# ou6_cs-ctrl_V1_0.net
KiCad netlist of a schematic drawn in EAGLE
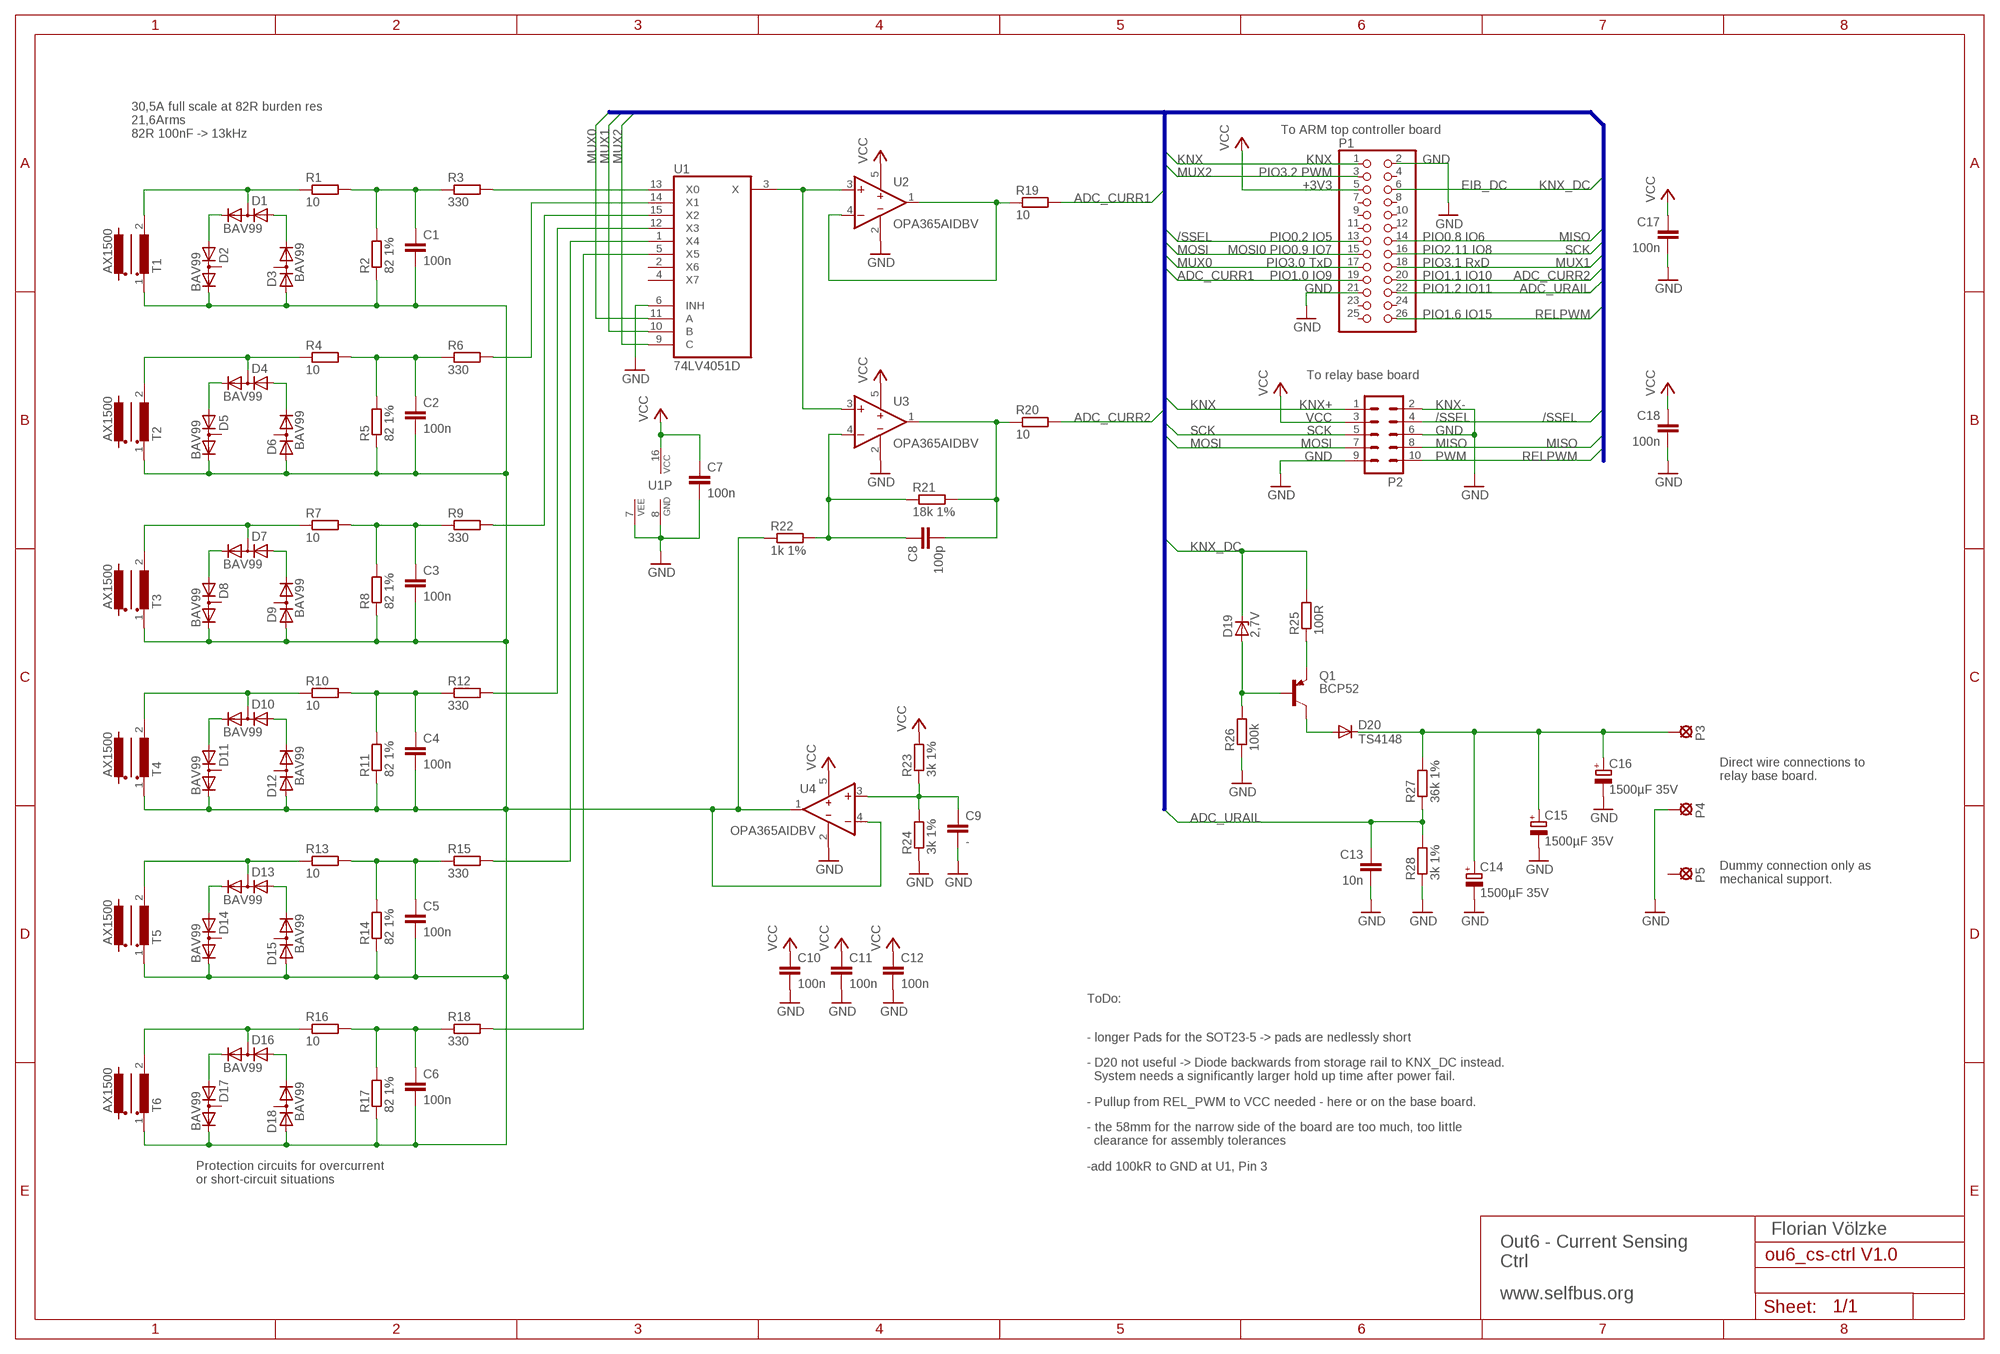
[diagram p0: schematic, sheet 1]

(export (version "E")
  (design (tool "Eeschema 10.0.6"))
  (components
    (comp (ref "C1")
      (value "100n")
      (footprint "eagle-import:R0805M")
      (libsource (lib "eagle-import") (part "C-EUC0805M"))
    )
    (comp (ref "C2")
      (value "100n")
      (footprint "eagle-import:R0805M")
      (libsource (lib "eagle-import") (part "C-EUC0805M"))
    )
    (comp (ref "C3")
      (value "100n")
      (footprint "eagle-import:R0805M")
      (libsource (lib "eagle-import") (part "C-EUC0805M"))
    )
    (comp (ref "C4")
      (value "100n")
      (footprint "eagle-import:R0805M")
      (libsource (lib "eagle-import") (part "C-EUC0805M"))
    )
    (comp (ref "C5")
      (value "100n")
      (footprint "eagle-import:R0805M")
      (libsource (lib "eagle-import") (part "C-EUC0805M"))
    )
    (comp (ref "C6")
      (value "100n")
      (footprint "eagle-import:R0805M")
      (libsource (lib "eagle-import") (part "C-EUC0805M"))
    )
    (comp (ref "C7")
      (value "100n")
      (footprint "eagle-import:R0805M")
      (libsource (lib "eagle-import") (part "C-EUC0805M"))
    )
    (comp (ref "C8")
      (value "100p")
      (footprint "eagle-import:R0805M")
      (libsource (lib "eagle-import") (part "C-EUC0805M"))
    )
    (comp (ref "C9")
      (value "-")
      (footprint "eagle-import:R0805M")
      (libsource (lib "eagle-import") (part "C-EUC0805M"))
    )
    (comp (ref "C10")
      (value "100n")
      (footprint "eagle-import:R0805M")
      (libsource (lib "eagle-import") (part "C-EUC0805M"))
    )
    (comp (ref "C11")
      (value "100n")
      (footprint "eagle-import:R0805M")
      (libsource (lib "eagle-import") (part "C-EUC0805M"))
    )
    (comp (ref "C12")
      (value "100n")
      (footprint "eagle-import:R0805M")
      (libsource (lib "eagle-import") (part "C-EUC0805M"))
    )
    (comp (ref "C13")
      (value "10n")
      (footprint "eagle-import:R0805M")
      (libsource (lib "eagle-import") (part "C-EUC0805M"))
    )
    (comp (ref "C14")
      (value "1500µF 35V")
      (footprint "eagle-import:E5-13-30")
      (libsource (lib "eagle-import") (part "CPOL-EUE5-13-30"))
    )
    (comp (ref "C15")
      (value "1500µF 35V")
      (footprint "eagle-import:E5-13-30")
      (libsource (lib "eagle-import") (part "CPOL-EUE5-13-30"))
    )
    (comp (ref "C16")
      (value "1500µF 35V")
      (footprint "eagle-import:E5-13-30")
      (libsource (lib "eagle-import") (part "CPOL-EUE5-13-30"))
    )
    (comp (ref "C17")
      (value "100n")
      (footprint "eagle-import:R0805M")
      (libsource (lib "eagle-import") (part "C-EUC0805M"))
    )
    (comp (ref "C18")
      (value "100n")
      (footprint "eagle-import:R0805M")
      (libsource (lib "eagle-import") (part "C-EUC0805M"))
    )
    (comp (ref "D1")
      (value "BAV99")
      (footprint "eagle-import:SOT23")
      (libsource (lib "eagle-import") (part "DIODE_2CACA-SOT23"))
    )
    (comp (ref "D2")
      (value "BAV99")
      (footprint "eagle-import:SOT23")
      (libsource (lib "eagle-import") (part "DIODE_2CACA-SOT23"))
    )
    (comp (ref "D3")
      (value "BAV99")
      (footprint "eagle-import:SOT23")
      (libsource (lib "eagle-import") (part "DIODE_2CACA-SOT23"))
    )
    (comp (ref "D4")
      (value "BAV99")
      (footprint "eagle-import:SOT23")
      (libsource (lib "eagle-import") (part "DIODE_2CACA-SOT23"))
    )
    (comp (ref "D5")
      (value "BAV99")
      (footprint "eagle-import:SOT23")
      (libsource (lib "eagle-import") (part "DIODE_2CACA-SOT23"))
    )
    (comp (ref "D6")
      (value "BAV99")
      (footprint "eagle-import:SOT23")
      (libsource (lib "eagle-import") (part "DIODE_2CACA-SOT23"))
    )
    (comp (ref "D7")
      (value "BAV99")
      (footprint "eagle-import:SOT23")
      (libsource (lib "eagle-import") (part "DIODE_2CACA-SOT23"))
    )
    (comp (ref "D8")
      (value "BAV99")
      (footprint "eagle-import:SOT23")
      (libsource (lib "eagle-import") (part "DIODE_2CACA-SOT23"))
    )
    (comp (ref "D9")
      (value "BAV99")
      (footprint "eagle-import:SOT23")
      (libsource (lib "eagle-import") (part "DIODE_2CACA-SOT23"))
    )
    (comp (ref "D10")
      (value "BAV99")
      (footprint "eagle-import:SOT23")
      (libsource (lib "eagle-import") (part "DIODE_2CACA-SOT23"))
    )
    (comp (ref "D11")
      (value "BAV99")
      (footprint "eagle-import:SOT23")
      (libsource (lib "eagle-import") (part "DIODE_2CACA-SOT23"))
    )
    (comp (ref "D12")
      (value "BAV99")
      (footprint "eagle-import:SOT23")
      (libsource (lib "eagle-import") (part "DIODE_2CACA-SOT23"))
    )
    (comp (ref "D13")
      (value "BAV99")
      (footprint "eagle-import:SOT23")
      (libsource (lib "eagle-import") (part "DIODE_2CACA-SOT23"))
    )
    (comp (ref "D14")
      (value "BAV99")
      (footprint "eagle-import:SOT23")
      (libsource (lib "eagle-import") (part "DIODE_2CACA-SOT23"))
    )
    (comp (ref "D15")
      (value "BAV99")
      (footprint "eagle-import:SOT23")
      (libsource (lib "eagle-import") (part "DIODE_2CACA-SOT23"))
    )
    (comp (ref "D16")
      (value "BAV99")
      (footprint "eagle-import:SOT23")
      (libsource (lib "eagle-import") (part "DIODE_2CACA-SOT23"))
    )
    (comp (ref "D17")
      (value "BAV99")
      (footprint "eagle-import:SOT23")
      (libsource (lib "eagle-import") (part "DIODE_2CACA-SOT23"))
    )
    (comp (ref "D18")
      (value "BAV99")
      (footprint "eagle-import:SOT23")
      (libsource (lib "eagle-import") (part "DIODE_2CACA-SOT23"))
    )
    (comp (ref "D19")
      (value "2,7V")
      (footprint "eagle-import:SOT23")
      (libsource (lib "eagle-import") (part "ZENER-DIODESOT23"))
    )
    (comp (ref "D20")
      (value "TS4148")
      (footprint "eagle-import:MINIMELF")
      (libsource (lib "eagle-import") (part "DIODE-MINIMELF"))
    )
    (comp (ref "P1")
      (value "PINHD-2X13SMD")
      (footprint "eagle-import:2X13SMD")
      (libsource (lib "eagle-import") (part "PINHD-2X13SMD"))
    )
    (comp (ref "P2")
      (value "ML10")
      (footprint "eagle-import:ML10")
      (libsource (lib "eagle-import") (part "ML10"))
    )
    (comp (ref "P3")
      (value "SE1.5")
      (footprint "eagle-import:SE15")
      (libsource (lib "eagle-import") (part "SE1.5"))
    )
    (comp (ref "P4")
      (value "SE1.5")
      (footprint "eagle-import:SE15")
      (libsource (lib "eagle-import") (part "SE1.5"))
    )
    (comp (ref "P5")
      (value "SE1.5")
      (footprint "eagle-import:SE15")
      (libsource (lib "eagle-import") (part "SE1.5"))
    )
    (comp (ref "Q1")
      (value "BCP52")
      (footprint "eagle-import:SOT223")
      (libsource (lib "eagle-import") (part "FZT753SMD"))
    )
    (comp (ref "R1")
      (value "10")
      (footprint "eagle-import:R0805M")
      (libsource (lib "eagle-import") (part "R-EU_R0805M"))
    )
    (comp (ref "R2")
      (value "82 1%")
      (footprint "eagle-import:R0805M")
      (libsource (lib "eagle-import") (part "R-EU_R0805M"))
    )
    (comp (ref "R3")
      (value "330")
      (footprint "eagle-import:R0805M")
      (libsource (lib "eagle-import") (part "R-EU_R0805M"))
    )
    (comp (ref "R4")
      (value "10")
      (footprint "eagle-import:R0805M")
      (libsource (lib "eagle-import") (part "R-EU_R0805M"))
    )
    (comp (ref "R5")
      (value "82 1%")
      (footprint "eagle-import:R0805M")
      (libsource (lib "eagle-import") (part "R-EU_R0805M"))
    )
    (comp (ref "R6")
      (value "330")
      (footprint "eagle-import:R0805M")
      (libsource (lib "eagle-import") (part "R-EU_R0805M"))
    )
    (comp (ref "R7")
      (value "10")
      (footprint "eagle-import:R0805M")
      (libsource (lib "eagle-import") (part "R-EU_R0805M"))
    )
    (comp (ref "R8")
      (value "82 1%")
      (footprint "eagle-import:R0805M")
      (libsource (lib "eagle-import") (part "R-EU_R0805M"))
    )
    (comp (ref "R9")
      (value "330")
      (footprint "eagle-import:R0805M")
      (libsource (lib "eagle-import") (part "R-EU_R0805M"))
    )
    (comp (ref "R10")
      (value "10")
      (footprint "eagle-import:R0805M")
      (libsource (lib "eagle-import") (part "R-EU_R0805M"))
    )
    (comp (ref "R11")
      (value "82 1%")
      (footprint "eagle-import:R0805M")
      (libsource (lib "eagle-import") (part "R-EU_R0805M"))
    )
    (comp (ref "R12")
      (value "330")
      (footprint "eagle-import:R0805M")
      (libsource (lib "eagle-import") (part "R-EU_R0805M"))
    )
    (comp (ref "R13")
      (value "10")
      (footprint "eagle-import:R0805M")
      (libsource (lib "eagle-import") (part "R-EU_R0805M"))
    )
    (comp (ref "R14")
      (value "82 1%")
      (footprint "eagle-import:R0805M")
      (libsource (lib "eagle-import") (part "R-EU_R0805M"))
    )
    (comp (ref "R15")
      (value "330")
      (footprint "eagle-import:R0805M")
      (libsource (lib "eagle-import") (part "R-EU_R0805M"))
    )
    (comp (ref "R16")
      (value "10")
      (footprint "eagle-import:R0805M")
      (libsource (lib "eagle-import") (part "R-EU_R0805M"))
    )
    (comp (ref "R17")
      (value "82 1%")
      (footprint "eagle-import:R0805M")
      (libsource (lib "eagle-import") (part "R-EU_R0805M"))
    )
    (comp (ref "R18")
      (value "330")
      (footprint "eagle-import:R0805M")
      (libsource (lib "eagle-import") (part "R-EU_R0805M"))
    )
    (comp (ref "R19")
      (value "10")
      (footprint "eagle-import:R0805M")
      (libsource (lib "eagle-import") (part "R-EU_R0805M"))
    )
    (comp (ref "R20")
      (value "10")
      (footprint "eagle-import:R0805M")
      (libsource (lib "eagle-import") (part "R-EU_R0805M"))
    )
    (comp (ref "R21")
      (value "18k 1%")
      (footprint "eagle-import:R0805M")
      (libsource (lib "eagle-import") (part "R-EU_R0805M"))
    )
    (comp (ref "R22")
      (value "1k 1%")
      (footprint "eagle-import:R0805M")
      (libsource (lib "eagle-import") (part "R-EU_R0805M"))
    )
    (comp (ref "R23")
      (value "3k 1%")
      (footprint "eagle-import:R0805M")
      (libsource (lib "eagle-import") (part "R-EU_R0805M"))
    )
    (comp (ref "R24")
      (value "3k 1%")
      (footprint "eagle-import:R0805M")
      (libsource (lib "eagle-import") (part "R-EU_R0805M"))
    )
    (comp (ref "R25")
      (value "100R")
      (footprint "eagle-import:R0805M")
      (libsource (lib "eagle-import") (part "R-EU_R0805M"))
    )
    (comp (ref "R26")
      (value "100k")
      (footprint "eagle-import:R0805M")
      (libsource (lib "eagle-import") (part "R-EU_R0805M"))
    )
    (comp (ref "R27")
      (value "36k 1%")
      (footprint "eagle-import:R0805M")
      (libsource (lib "eagle-import") (part "R-EU_R0805M"))
    )
    (comp (ref "R28")
      (value "3k 1%")
      (footprint "eagle-import:R0805M")
      (libsource (lib "eagle-import") (part "R-EU_R0805M"))
    )
    (comp (ref "T1")
      (value "AX1500")
      (footprint "eagle-import:SMALLXFORMER")
      (libsource (lib "eagle-import") (part "STROMWANDLERTALEMA_AX1500"))
    )
    (comp (ref "T2")
      (value "AX1500")
      (footprint "eagle-import:SMALLXFORMER")
      (libsource (lib "eagle-import") (part "STROMWANDLERTALEMA_AX1500"))
    )
    (comp (ref "T3")
      (value "AX1500")
      (footprint "eagle-import:SMALLXFORMER")
      (libsource (lib "eagle-import") (part "STROMWANDLERTALEMA_AX1500"))
    )
    (comp (ref "T4")
      (value "AX1500")
      (footprint "eagle-import:SMALLXFORMER")
      (libsource (lib "eagle-import") (part "STROMWANDLERTALEMA_AX1500"))
    )
    (comp (ref "T5")
      (value "AX1500")
      (footprint "eagle-import:SMALLXFORMER")
      (libsource (lib "eagle-import") (part "STROMWANDLERTALEMA_AX1500"))
    )
    (comp (ref "T6")
      (value "AX1500")
      (footprint "eagle-import:SMALLXFORMER")
      (libsource (lib "eagle-import") (part "STROMWANDLERTALEMA_AX1500"))
    )
    (comp (ref "U1")
      (value "74LV4051D")
      (footprint "eagle-import:SO16")
      (libsource (lib "eagle-import") (part "4051D"))
    )
    (comp (ref "U2")
      (value "OPA365AIDBV")
      (footprint "eagle-import:SOT23-5")
      (libsource (lib "eagle-import") (part "LTC2050CS5"))
    )
    (comp (ref "U3")
      (value "OPA365AIDBV")
      (footprint "eagle-import:SOT23-5")
      (libsource (lib "eagle-import") (part "LTC2050CS5"))
    )
    (comp (ref "U4")
      (value "OPA365AIDBV")
      (footprint "eagle-import:SOT23-5")
      (libsource (lib "eagle-import") (part "LTC2050CS5"))
    )
  )
  (nets
    (net (code "1") (name "/ADC_CURR1") (class "Default")
      (node (ref "P1") (pin "19") (pinfunction "19_19") (pintype "passive"))
      (node (ref "R19") (pin "2") (pinfunction "2_2") (pintype "passive"))
    )
    (net (code "2") (name "/ADC_CURR2") (class "Default")
      (node (ref "P1") (pin "20") (pinfunction "20_20") (pintype "passive"))
      (node (ref "R20") (pin "2") (pinfunction "2_2") (pintype "passive"))
    )
    (net (code "3") (name "/ADC_URAIL") (class "Default")
      (node (ref "C13") (pin "1") (pinfunction "1_1") (pintype "passive"))
      (node (ref "P1") (pin "22") (pinfunction "22_22") (pintype "passive"))
      (node (ref "R27") (pin "1") (pinfunction "1_1") (pintype "passive"))
      (node (ref "R28") (pin "2") (pinfunction "2_2") (pintype "passive"))
    )
    (net (code "4") (name "/KNX") (class "Default")
      (node (ref "P1") (pin "1") (pinfunction "1_1") (pintype "passive"))
      (node (ref "P2") (pin "1") (pinfunction "1_1") (pintype "passive"))
    )
    (net (code "5") (name "/KNX_DC") (class "Default")
      (node (ref "D19") (pin "3") (pinfunction "C_3") (pintype "passive"))
      (node (ref "P1") (pin "6") (pinfunction "6_6") (pintype "passive"))
      (node (ref "R25") (pin "2") (pinfunction "2_2") (pintype "passive"))
    )
    (net (code "6") (name "/MISO") (class "Default")
      (node (ref "P1") (pin "14") (pinfunction "14_14") (pintype "passive"))
      (node (ref "P2") (pin "8") (pinfunction "8_8") (pintype "passive"))
    )
    (net (code "7") (name "/MOSI") (class "Default")
      (node (ref "P1") (pin "15") (pinfunction "15_15") (pintype "passive"))
      (node (ref "P2") (pin "7") (pinfunction "7_7") (pintype "passive"))
    )
    (net (code "8") (name "/MUX0") (class "Default")
      (node (ref "P1") (pin "17") (pinfunction "17_17") (pintype "passive"))
      (node (ref "U1") (pin "11") (pinfunction "A_11") (pintype "input"))
    )
    (net (code "9") (name "/MUX1") (class "Default")
      (node (ref "P1") (pin "18") (pinfunction "18_18") (pintype "passive"))
      (node (ref "U1") (pin "10") (pinfunction "B_10") (pintype "input"))
    )
    (net (code "10") (name "/MUX2") (class "Default")
      (node (ref "P1") (pin "3") (pinfunction "3_3") (pintype "passive"))
      (node (ref "U1") (pin "9") (pinfunction "C_9") (pintype "input"))
    )
    (net (code "11") (name "/RELPWM") (class "Default")
      (node (ref "P1") (pin "26") (pinfunction "26_26") (pintype "passive"))
      (node (ref "P2") (pin "10") (pinfunction "10_10") (pintype "passive"))
    )
    (net (code "12") (name "/SCK") (class "Default")
      (node (ref "P1") (pin "16") (pinfunction "16_16") (pintype "passive"))
      (node (ref "P2") (pin "5") (pinfunction "5_5") (pintype "passive"))
    )
    (net (code "13") (name "/{slash}SSEL") (class "Default")
      (node (ref "P1") (pin "13") (pinfunction "13_13") (pintype "passive"))
      (node (ref "P2") (pin "4") (pinfunction "4_4") (pintype "passive"))
    )
    (net (code "14") (name "GND") (class "Default")
      (node (ref "C10") (pin "2") (pinfunction "2_2") (pintype "passive"))
      (node (ref "C11") (pin "2") (pinfunction "2_2") (pintype "passive"))
      (node (ref "C12") (pin "2") (pinfunction "2_2") (pintype "passive"))
      (node (ref "C13") (pin "2") (pinfunction "2_2") (pintype "passive"))
      (node (ref "C14") (pin "-") (pinfunction "-_-") (pintype "passive"))
      (node (ref "C15") (pin "-") (pinfunction "-_-") (pintype "passive"))
      (node (ref "C16") (pin "-") (pinfunction "-_-") (pintype "passive"))
      (node (ref "C17") (pin "2") (pinfunction "2_2") (pintype "passive"))
      (node (ref "C18") (pin "2") (pinfunction "2_2") (pintype "passive"))
      (node (ref "C7") (pin "2") (pinfunction "2_2") (pintype "passive"))
      (node (ref "C9") (pin "2") (pinfunction "2_2") (pintype "passive"))
      (node (ref "P1") (pin "2") (pinfunction "2_2") (pintype "passive"))
      (node (ref "P1") (pin "21") (pinfunction "21_21") (pintype "passive"))
      (node (ref "P2") (pin "2") (pinfunction "2_2") (pintype "passive"))
      (node (ref "P2") (pin "6") (pinfunction "6_6") (pintype "passive"))
      (node (ref "P2") (pin "9") (pinfunction "9_9") (pintype "passive"))
      (node (ref "P4") (pin "MP") (pinfunction "MP_MP") (pintype "passive"))
      (node (ref "R24") (pin "1") (pinfunction "1_1") (pintype "passive"))
      (node (ref "R26") (pin "1") (pinfunction "1_1") (pintype "passive"))
      (node (ref "R28") (pin "1") (pinfunction "1_1") (pintype "passive"))
      (node (ref "U1") (pin "6") (pinfunction "INH_6") (pintype "input"))
      (node (ref "U1") (pin "7") (pinfunction "VEE_7") (pintype "power_in"))
      (node (ref "U1") (pin "8") (pinfunction "GND_8") (pintype "power_in"))
      (node (ref "U2") (pin "2") (pinfunction "V-_2") (pintype "power_in"))
      (node (ref "U3") (pin "2") (pinfunction "V-_2") (pintype "power_in"))
      (node (ref "U4") (pin "2") (pinfunction "V-_2") (pintype "power_in"))
    )
    (net (code "15") (name "Net-(C1-Pad1)") (class "Default")
      (node (ref "C1") (pin "1") (pinfunction "1_1") (pintype "passive"))
      (node (ref "R1") (pin "2") (pinfunction "2_2") (pintype "passive"))
      (node (ref "R2") (pin "2") (pinfunction "2_2") (pintype "passive"))
      (node (ref "R3") (pin "1") (pinfunction "1_1") (pintype "passive"))
    )
    (net (code "16") (name "Net-(C2-Pad1)") (class "Default")
      (node (ref "C2") (pin "1") (pinfunction "1_1") (pintype "passive"))
      (node (ref "R4") (pin "2") (pinfunction "2_2") (pintype "passive"))
      (node (ref "R5") (pin "2") (pinfunction "2_2") (pintype "passive"))
      (node (ref "R6") (pin "1") (pinfunction "1_1") (pintype "passive"))
    )
    (net (code "17") (name "Net-(C3-Pad1)") (class "Default")
      (node (ref "C3") (pin "1") (pinfunction "1_1") (pintype "passive"))
      (node (ref "R7") (pin "2") (pinfunction "2_2") (pintype "passive"))
      (node (ref "R8") (pin "2") (pinfunction "2_2") (pintype "passive"))
      (node (ref "R9") (pin "1") (pinfunction "1_1") (pintype "passive"))
    )
    (net (code "18") (name "Net-(C4-Pad1)") (class "Default")
      (node (ref "C4") (pin "1") (pinfunction "1_1") (pintype "passive"))
      (node (ref "R10") (pin "2") (pinfunction "2_2") (pintype "passive"))
      (node (ref "R11") (pin "2") (pinfunction "2_2") (pintype "passive"))
      (node (ref "R12") (pin "1") (pinfunction "1_1") (pintype "passive"))
    )
    (net (code "19") (name "Net-(C5-Pad1)") (class "Default")
      (node (ref "C5") (pin "1") (pinfunction "1_1") (pintype "passive"))
      (node (ref "R13") (pin "2") (pinfunction "2_2") (pintype "passive"))
      (node (ref "R14") (pin "2") (pinfunction "2_2") (pintype "passive"))
      (node (ref "R15") (pin "1") (pinfunction "1_1") (pintype "passive"))
    )
    (net (code "20") (name "Net-(C6-Pad1)") (class "Default")
      (node (ref "C6") (pin "1") (pinfunction "1_1") (pintype "passive"))
      (node (ref "R16") (pin "2") (pinfunction "2_2") (pintype "passive"))
      (node (ref "R17") (pin "2") (pinfunction "2_2") (pintype "passive"))
      (node (ref "R18") (pin "1") (pinfunction "1_1") (pintype "passive"))
    )
    (net (code "21") (name "Net-(C14-Pad+)") (class "Default")
      (node (ref "C14") (pin "+") (pinfunction "+_+") (pintype "passive"))
      (node (ref "C15") (pin "+") (pinfunction "+_+") (pintype "passive"))
      (node (ref "C16") (pin "+") (pinfunction "+_+") (pintype "passive"))
      (node (ref "D20") (pin "C") (pinfunction "C_C") (pintype "passive"))
      (node (ref "P3") (pin "MP") (pinfunction "MP_MP") (pintype "passive"))
      (node (ref "R27") (pin "2") (pinfunction "2_2") (pintype "passive"))
    )
    (net (code "22") (name "Net-(D1-A)") (class "Default")
      (node (ref "D1") (pin "1") (pinfunction "A_1") (pintype "passive"))
      (node (ref "D3") (pin "2") (pinfunction "C_2") (pintype "passive"))
    )
    (net (code "23") (name "Net-(D1-AC)") (class "Default")
      (node (ref "D1") (pin "3") (pinfunction "AC_3") (pintype "passive"))
      (node (ref "R1") (pin "1") (pinfunction "1_1") (pintype "passive"))
      (node (ref "T1") (pin "2") (pinfunction "W1E_2") (pintype "passive"))
    )
    (net (code "24") (name "Net-(D1-C)") (class "Default")
      (node (ref "D1") (pin "2") (pinfunction "C_2") (pintype "passive"))
      (node (ref "D2") (pin "1") (pinfunction "A_1") (pintype "passive"))
    )
    (net (code "25") (name "Net-(D4-A)") (class "Default")
      (node (ref "D4") (pin "1") (pinfunction "A_1") (pintype "passive"))
      (node (ref "D6") (pin "2") (pinfunction "C_2") (pintype "passive"))
    )
    (net (code "26") (name "Net-(D4-AC)") (class "Default")
      (node (ref "D4") (pin "3") (pinfunction "AC_3") (pintype "passive"))
      (node (ref "R4") (pin "1") (pinfunction "1_1") (pintype "passive"))
      (node (ref "T2") (pin "2") (pinfunction "W1E_2") (pintype "passive"))
    )
    (net (code "27") (name "Net-(D4-C)") (class "Default")
      (node (ref "D4") (pin "2") (pinfunction "C_2") (pintype "passive"))
      (node (ref "D5") (pin "1") (pinfunction "A_1") (pintype "passive"))
    )
    (net (code "28") (name "Net-(D7-A)") (class "Default")
      (node (ref "D7") (pin "1") (pinfunction "A_1") (pintype "passive"))
      (node (ref "D9") (pin "2") (pinfunction "C_2") (pintype "passive"))
    )
    (net (code "29") (name "Net-(D7-AC)") (class "Default")
      (node (ref "D7") (pin "3") (pinfunction "AC_3") (pintype "passive"))
      (node (ref "R7") (pin "1") (pinfunction "1_1") (pintype "passive"))
      (node (ref "T3") (pin "2") (pinfunction "W1E_2") (pintype "passive"))
    )
    (net (code "30") (name "Net-(D7-C)") (class "Default")
      (node (ref "D7") (pin "2") (pinfunction "C_2") (pintype "passive"))
      (node (ref "D8") (pin "1") (pinfunction "A_1") (pintype "passive"))
    )
    (net (code "31") (name "Net-(D10-A)") (class "Default")
      (node (ref "D10") (pin "1") (pinfunction "A_1") (pintype "passive"))
      (node (ref "D12") (pin "2") (pinfunction "C_2") (pintype "passive"))
    )
    (net (code "32") (name "Net-(D10-AC)") (class "Default")
      (node (ref "D10") (pin "3") (pinfunction "AC_3") (pintype "passive"))
      (node (ref "R10") (pin "1") (pinfunction "1_1") (pintype "passive"))
      (node (ref "T4") (pin "2") (pinfunction "W1E_2") (pintype "passive"))
    )
    (net (code "33") (name "Net-(D10-C)") (class "Default")
      (node (ref "D10") (pin "2") (pinfunction "C_2") (pintype "passive"))
      (node (ref "D11") (pin "1") (pinfunction "A_1") (pintype "passive"))
    )
    (net (code "34") (name "Net-(D11-C)") (class "Default")
      (node (ref "C1") (pin "2") (pinfunction "2_2") (pintype "passive"))
      (node (ref "C2") (pin "2") (pinfunction "2_2") (pintype "passive"))
      (node (ref "C3") (pin "2") (pinfunction "2_2") (pintype "passive"))
      (node (ref "C4") (pin "2") (pinfunction "2_2") (pintype "passive"))
      (node (ref "C5") (pin "2") (pinfunction "2_2") (pintype "passive"))
      (node (ref "C6") (pin "2") (pinfunction "2_2") (pintype "passive"))
      (node (ref "D11") (pin "2") (pinfunction "C_2") (pintype "passive"))
      (node (ref "D12") (pin "1") (pinfunction "A_1") (pintype "passive"))
      (node (ref "D14") (pin "2") (pinfunction "C_2") (pintype "passive"))
      (node (ref "D15") (pin "1") (pinfunction "A_1") (pintype "passive"))
      (node (ref "D17") (pin "2") (pinfunction "C_2") (pintype "passive"))
      (node (ref "D18") (pin "1") (pinfunction "A_1") (pintype "passive"))
      (node (ref "D2") (pin "2") (pinfunction "C_2") (pintype "passive"))
      (node (ref "D3") (pin "1") (pinfunction "A_1") (pintype "passive"))
      (node (ref "D5") (pin "2") (pinfunction "C_2") (pintype "passive"))
      (node (ref "D6") (pin "1") (pinfunction "A_1") (pintype "passive"))
      (node (ref "D8") (pin "2") (pinfunction "C_2") (pintype "passive"))
      (node (ref "D9") (pin "1") (pinfunction "A_1") (pintype "passive"))
      (node (ref "R11") (pin "1") (pinfunction "1_1") (pintype "passive"))
      (node (ref "R14") (pin "1") (pinfunction "1_1") (pintype "passive"))
      (node (ref "R17") (pin "1") (pinfunction "1_1") (pintype "passive"))
      (node (ref "R2") (pin "1") (pinfunction "1_1") (pintype "passive"))
      (node (ref "R22") (pin "1") (pinfunction "1_1") (pintype "passive"))
      (node (ref "R5") (pin "1") (pinfunction "1_1") (pintype "passive"))
      (node (ref "R8") (pin "1") (pinfunction "1_1") (pintype "passive"))
      (node (ref "T1") (pin "1") (pinfunction "W1A_1") (pintype "passive"))
      (node (ref "T2") (pin "1") (pinfunction "W1A_1") (pintype "passive"))
      (node (ref "T3") (pin "1") (pinfunction "W1A_1") (pintype "passive"))
      (node (ref "T4") (pin "1") (pinfunction "W1A_1") (pintype "passive"))
      (node (ref "T5") (pin "1") (pinfunction "W1A_1") (pintype "passive"))
      (node (ref "T6") (pin "1") (pinfunction "W1A_1") (pintype "passive"))
      (node (ref "U4") (pin "1") (pinfunction "OUT_1") (pintype "output"))
      (node (ref "U4") (pin "4") (pinfunction "-IN_4") (pintype "input"))
    )
    (net (code "35") (name "Net-(D13-A)") (class "Default")
      (node (ref "D13") (pin "1") (pinfunction "A_1") (pintype "passive"))
      (node (ref "D15") (pin "2") (pinfunction "C_2") (pintype "passive"))
    )
    (net (code "36") (name "Net-(D13-AC)") (class "Default")
      (node (ref "D13") (pin "3") (pinfunction "AC_3") (pintype "passive"))
      (node (ref "R13") (pin "1") (pinfunction "1_1") (pintype "passive"))
      (node (ref "T5") (pin "2") (pinfunction "W1E_2") (pintype "passive"))
    )
    (net (code "37") (name "Net-(D13-C)") (class "Default")
      (node (ref "D13") (pin "2") (pinfunction "C_2") (pintype "passive"))
      (node (ref "D14") (pin "1") (pinfunction "A_1") (pintype "passive"))
    )
    (net (code "38") (name "Net-(D16-A)") (class "Default")
      (node (ref "D16") (pin "1") (pinfunction "A_1") (pintype "passive"))
      (node (ref "D18") (pin "2") (pinfunction "C_2") (pintype "passive"))
    )
    (net (code "39") (name "Net-(D16-AC)") (class "Default")
      (node (ref "D16") (pin "3") (pinfunction "AC_3") (pintype "passive"))
      (node (ref "R16") (pin "1") (pinfunction "1_1") (pintype "passive"))
      (node (ref "T6") (pin "2") (pinfunction "W1E_2") (pintype "passive"))
    )
    (net (code "40") (name "Net-(D16-C)") (class "Default")
      (node (ref "D16") (pin "2") (pinfunction "C_2") (pintype "passive"))
      (node (ref "D17") (pin "1") (pinfunction "A_1") (pintype "passive"))
    )
    (net (code "41") (name "Net-(D19-A)") (class "Default")
      (node (ref "D19") (pin "1") (pinfunction "A_1") (pintype "passive"))
      (node (ref "Q1") (pin "1") (pinfunction "B_1") (pintype "passive"))
      (node (ref "R26") (pin "2") (pinfunction "2_2") (pintype "passive"))
    )
    (net (code "42") (name "Net-(D20-PadA)") (class "Default")
      (node (ref "D20") (pin "A") (pinfunction "A_A") (pintype "passive"))
      (node (ref "Q1") (pin "2") (pinfunction "C_2") (pintype "passive"))
      (node (ref "Q1") (pin "4") (pinfunction "C_4") (pintype "passive"))
    )
    (net (code "43") (name "Net-(Q1-E)") (class "Default")
      (node (ref "Q1") (pin "3") (pinfunction "E_3") (pintype "passive"))
      (node (ref "R25") (pin "1") (pinfunction "1_1") (pintype "passive"))
    )
    (net (code "44") (name "Net-(U1A-X)") (class "Default")
      (node (ref "U1") (pin "3") (pinfunction "X_3") (pintype "bidirectional"))
      (node (ref "U2") (pin "3") (pinfunction "+IN_3") (pintype "input"))
      (node (ref "U3") (pin "3") (pinfunction "+IN_3") (pintype "input"))
    )
    (net (code "45") (name "Net-(U1A-X0)") (class "Default")
      (node (ref "R3") (pin "2") (pinfunction "2_2") (pintype "passive"))
      (node (ref "U1") (pin "13") (pinfunction "X0_13") (pintype "bidirectional"))
    )
    (net (code "46") (name "Net-(U1A-X1)") (class "Default")
      (node (ref "R6") (pin "2") (pinfunction "2_2") (pintype "passive"))
      (node (ref "U1") (pin "14") (pinfunction "X1_14") (pintype "bidirectional"))
    )
    (net (code "47") (name "Net-(U1A-X2)") (class "Default")
      (node (ref "R9") (pin "2") (pinfunction "2_2") (pintype "passive"))
      (node (ref "U1") (pin "15") (pinfunction "X2_15") (pintype "bidirectional"))
    )
    (net (code "48") (name "Net-(U1A-X3)") (class "Default")
      (node (ref "R12") (pin "2") (pinfunction "2_2") (pintype "passive"))
      (node (ref "U1") (pin "12") (pinfunction "X3_12") (pintype "bidirectional"))
    )
    (net (code "49") (name "Net-(U1A-X4)") (class "Default")
      (node (ref "R15") (pin "2") (pinfunction "2_2") (pintype "passive"))
      (node (ref "U1") (pin "1") (pinfunction "X4_1") (pintype "bidirectional"))
    )
    (net (code "50") (name "Net-(U1A-X5)") (class "Default")
      (node (ref "R18") (pin "2") (pinfunction "2_2") (pintype "passive"))
      (node (ref "U1") (pin "5") (pinfunction "X5_5") (pintype "bidirectional"))
    )
    (net (code "51") (name "Net-(U2--IN)") (class "Default")
      (node (ref "R19") (pin "1") (pinfunction "1_1") (pintype "passive"))
      (node (ref "U2") (pin "1") (pinfunction "OUT_1") (pintype "output"))
      (node (ref "U2") (pin "4") (pinfunction "-IN_4") (pintype "input"))
    )
    (net (code "52") (name "Net-(U3--IN)") (class "Default")
      (node (ref "C8") (pin "1") (pinfunction "1_1") (pintype "passive"))
      (node (ref "R21") (pin "1") (pinfunction "1_1") (pintype "passive"))
      (node (ref "R22") (pin "2") (pinfunction "2_2") (pintype "passive"))
      (node (ref "U3") (pin "4") (pinfunction "-IN_4") (pintype "input"))
    )
    (net (code "53") (name "Net-(U3-OUT)") (class "Default")
      (node (ref "C8") (pin "2") (pinfunction "2_2") (pintype "passive"))
      (node (ref "R20") (pin "1") (pinfunction "1_1") (pintype "passive"))
      (node (ref "R21") (pin "2") (pinfunction "2_2") (pintype "passive"))
      (node (ref "U3") (pin "1") (pinfunction "OUT_1") (pintype "output"))
    )
    (net (code "54") (name "Net-(U4-+IN)") (class "Default")
      (node (ref "C9") (pin "1") (pinfunction "1_1") (pintype "passive"))
      (node (ref "R23") (pin "1") (pinfunction "1_1") (pintype "passive"))
      (node (ref "R24") (pin "2") (pinfunction "2_2") (pintype "passive"))
      (node (ref "U4") (pin "3") (pinfunction "+IN_3") (pintype "input"))
    )
    (net (code "55") (name "VCC") (class "Default")
      (node (ref "C10") (pin "1") (pinfunction "1_1") (pintype "passive"))
      (node (ref "C11") (pin "1") (pinfunction "1_1") (pintype "passive"))
      (node (ref "C12") (pin "1") (pinfunction "1_1") (pintype "passive"))
      (node (ref "C17") (pin "1") (pinfunction "1_1") (pintype "passive"))
      (node (ref "C18") (pin "1") (pinfunction "1_1") (pintype "passive"))
      (node (ref "C7") (pin "1") (pinfunction "1_1") (pintype "passive"))
      (node (ref "P1") (pin "5") (pinfunction "5_5") (pintype "passive"))
      (node (ref "P2") (pin "3") (pinfunction "3_3") (pintype "passive"))
      (node (ref "R23") (pin "2") (pinfunction "2_2") (pintype "passive"))
      (node (ref "U1") (pin "16") (pinfunction "VCC_16") (pintype "power_in"))
      (node (ref "U2") (pin "5") (pinfunction "V+_5") (pintype "power_in"))
      (node (ref "U3") (pin "5") (pinfunction "V+_5") (pintype "power_in"))
      (node (ref "U4") (pin "5") (pinfunction "V+_5") (pintype "power_in"))
    )
    (net (code "56") (name "unconnected-(D2-AC-Pad3)") (class "Default")
      (node (ref "D2") (pin "3") (pinfunction "AC_3") (pintype "passive"))
    )
    (net (code "57") (name "unconnected-(D3-AC-Pad3)") (class "Default")
      (node (ref "D3") (pin "3") (pinfunction "AC_3") (pintype "passive"))
    )
    (net (code "58") (name "unconnected-(D5-AC-Pad3)") (class "Default")
      (node (ref "D5") (pin "3") (pinfunction "AC_3") (pintype "passive"))
    )
    (net (code "59") (name "unconnected-(D6-AC-Pad3)") (class "Default")
      (node (ref "D6") (pin "3") (pinfunction "AC_3") (pintype "passive"))
    )
    (net (code "60") (name "unconnected-(D8-AC-Pad3)") (class "Default")
      (node (ref "D8") (pin "3") (pinfunction "AC_3") (pintype "passive"))
    )
    (net (code "61") (name "unconnected-(D9-AC-Pad3)") (class "Default")
      (node (ref "D9") (pin "3") (pinfunction "AC_3") (pintype "passive"))
    )
    (net (code "62") (name "unconnected-(D11-AC-Pad3)") (class "Default")
      (node (ref "D11") (pin "3") (pinfunction "AC_3") (pintype "passive"))
    )
    (net (code "63") (name "unconnected-(D12-AC-Pad3)") (class "Default")
      (node (ref "D12") (pin "3") (pinfunction "AC_3") (pintype "passive"))
    )
    (net (code "64") (name "unconnected-(D14-AC-Pad3)") (class "Default")
      (node (ref "D14") (pin "3") (pinfunction "AC_3") (pintype "passive"))
    )
    (net (code "65") (name "unconnected-(D15-AC-Pad3)") (class "Default")
      (node (ref "D15") (pin "3") (pinfunction "AC_3") (pintype "passive"))
    )
    (net (code "66") (name "unconnected-(D17-AC-Pad3)") (class "Default")
      (node (ref "D17") (pin "3") (pinfunction "AC_3") (pintype "passive"))
    )
    (net (code "67") (name "unconnected-(D18-AC-Pad3)") (class "Default")
      (node (ref "D18") (pin "3") (pinfunction "AC_3") (pintype "passive"))
    )
    (net (code "68") (name "unconnected-(P1-Pad4)") (class "Default")
      (node (ref "P1") (pin "4") (pinfunction "4_4") (pintype "passive"))
    )
    (net (code "69") (name "unconnected-(P1-Pad7)") (class "Default")
      (node (ref "P1") (pin "7") (pinfunction "7_7") (pintype "passive"))
    )
    (net (code "70") (name "unconnected-(P1-Pad8)") (class "Default")
      (node (ref "P1") (pin "8") (pinfunction "8_8") (pintype "passive"))
    )
    (net (code "71") (name "unconnected-(P1-Pad9)") (class "Default")
      (node (ref "P1") (pin "9") (pinfunction "9_9") (pintype "passive"))
    )
    (net (code "72") (name "unconnected-(P1-Pad10)") (class "Default")
      (node (ref "P1") (pin "10") (pinfunction "10_10") (pintype "passive"))
    )
    (net (code "73") (name "unconnected-(P1-Pad11)") (class "Default")
      (node (ref "P1") (pin "11") (pinfunction "11_11") (pintype "passive"))
    )
    (net (code "74") (name "unconnected-(P1-Pad12)") (class "Default")
      (node (ref "P1") (pin "12") (pinfunction "12_12") (pintype "passive"))
    )
    (net (code "75") (name "unconnected-(P1-Pad23)") (class "Default")
      (node (ref "P1") (pin "23") (pinfunction "23_23") (pintype "passive"))
    )
    (net (code "76") (name "unconnected-(P1-Pad24)") (class "Default")
      (node (ref "P1") (pin "24") (pinfunction "24_24") (pintype "passive"))
    )
    (net (code "77") (name "unconnected-(P1-Pad25)") (class "Default")
      (node (ref "P1") (pin "25") (pinfunction "25_25") (pintype "passive"))
    )
    (net (code "78") (name "unconnected-(P5-PadMP)") (class "Default")
      (node (ref "P5") (pin "MP") (pinfunction "MP_MP") (pintype "passive"))
    )
    (net (code "79") (name "unconnected-(U1A-X6-Pad2)") (class "Default")
      (node (ref "U1") (pin "2") (pinfunction "X6_2") (pintype "bidirectional"))
    )
    (net (code "80") (name "unconnected-(U1A-X7-Pad4)") (class "Default")
      (node (ref "U1") (pin "4") (pinfunction "X7_4") (pintype "bidirectional"))
    )
  )
)
